# Filamint_Schematic_V4_5.net
KiCad netlist of a schematic drawn in EAGLE
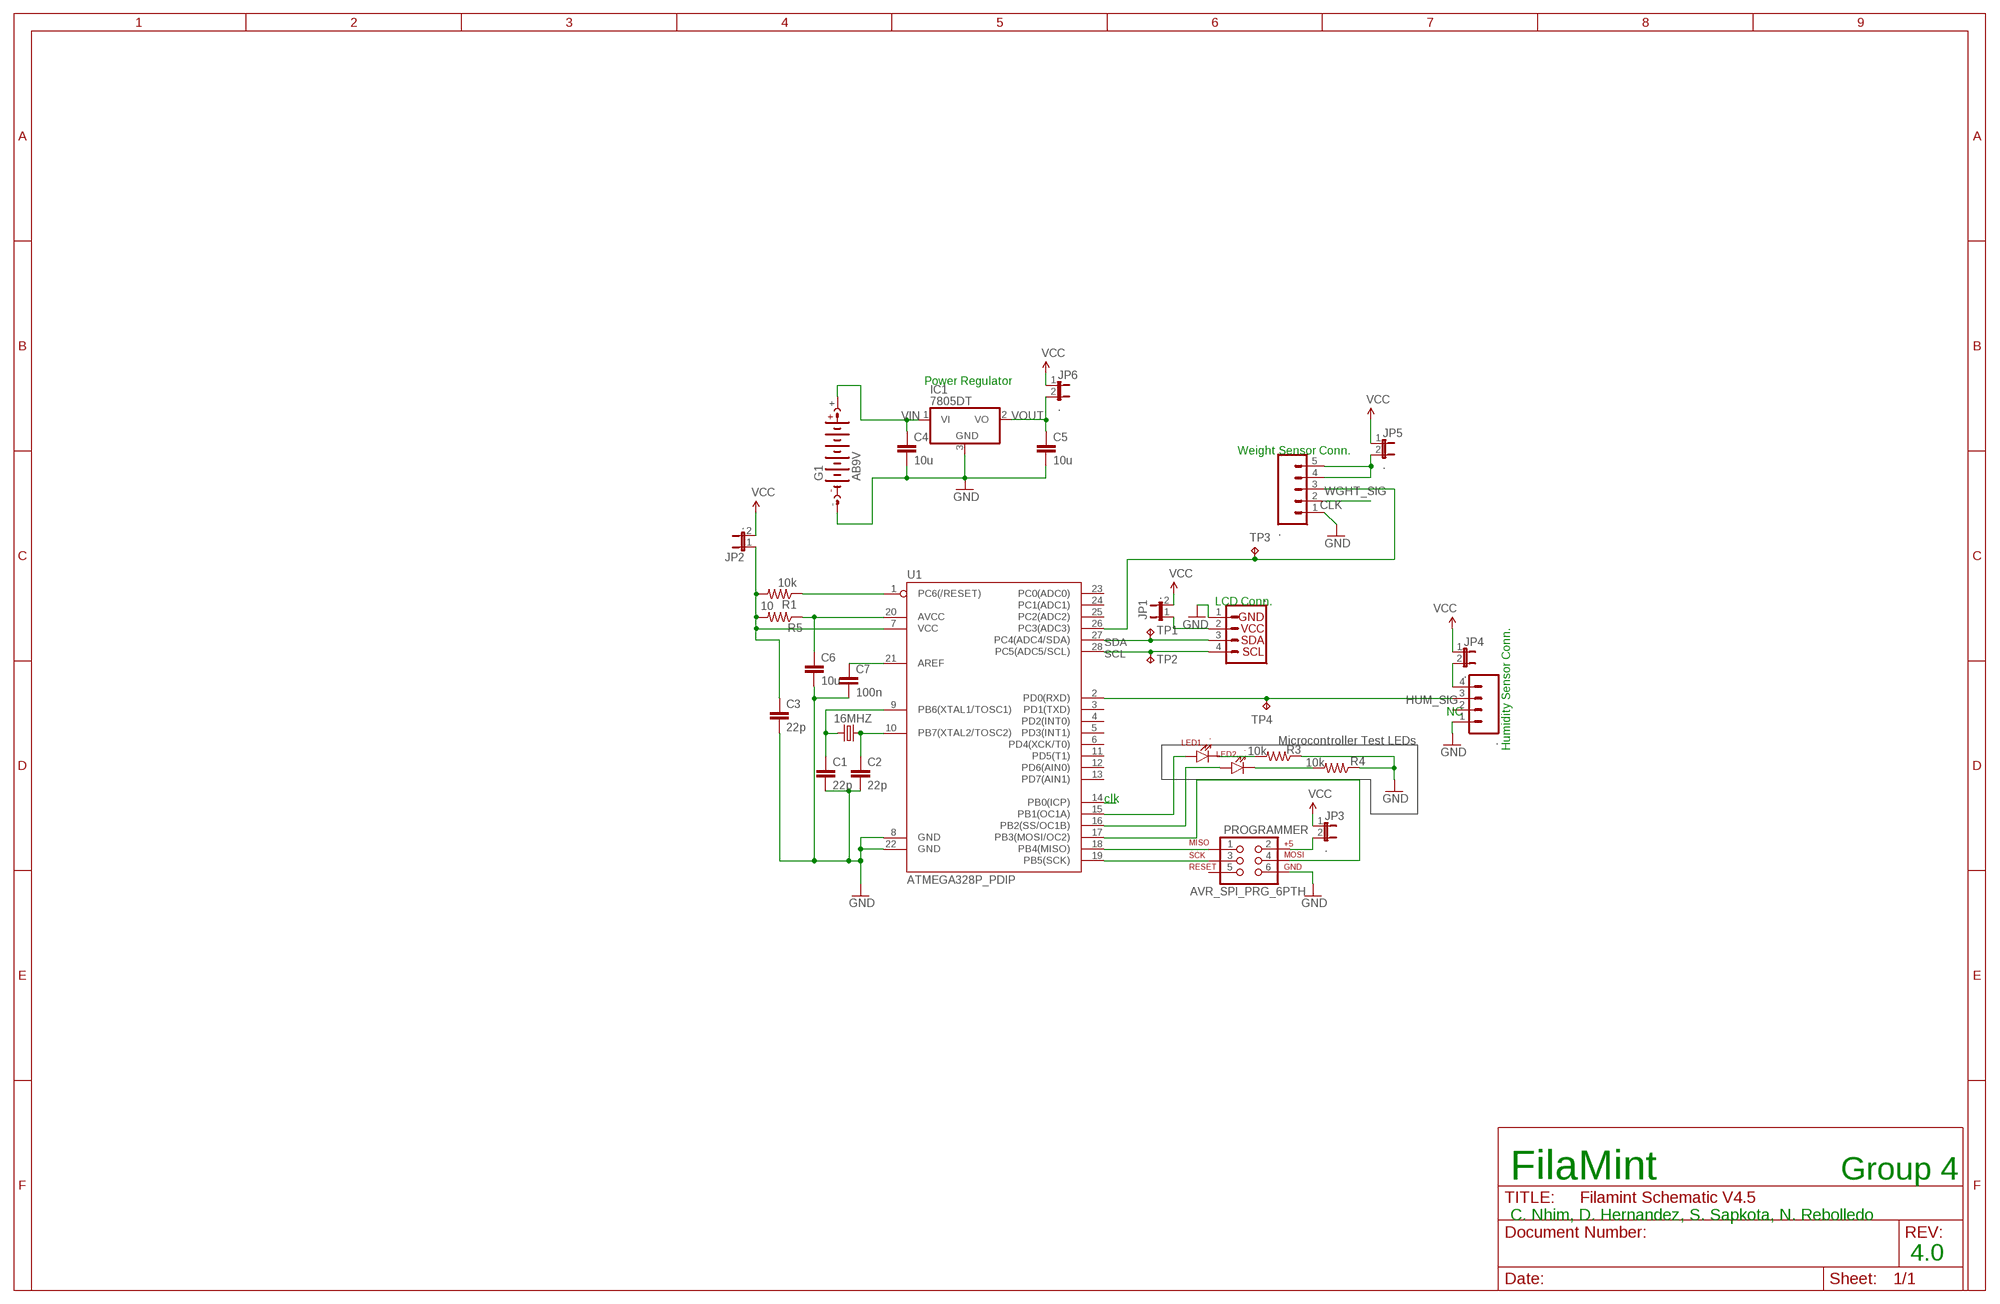
[diagram p0: schematic, sheet 1]

(export (version "E")
  (design (tool "Eeschema 10.0.6"))
  (components
    (comp (ref "16MHZ")
      (value "CSM-7X-DU")
      (footprint "eagle-import:CSM-7X-DU")
      (libsource (lib "eagle-import") (part "CSM-7X-DU"))
    )
    (comp (ref "C1")
      (value "22p")
      (footprint "eagle-import:C025-024X044")
      (libsource (lib "eagle-import") (part "C-EU025-024X044"))
    )
    (comp (ref "C2")
      (value "22p")
      (footprint "eagle-import:C025-024X044")
      (libsource (lib "eagle-import") (part "C-EU025-024X044"))
    )
    (comp (ref "C3")
      (value "22p")
      (footprint "eagle-import:C025-024X044")
      (libsource (lib "eagle-import") (part "C-EU025-024X044"))
    )
    (comp (ref "C4")
      (value "10u")
      (footprint "eagle-import:C025-024X044")
      (libsource (lib "eagle-import") (part "C-EU025-024X044"))
    )
    (comp (ref "C5")
      (value "10u")
      (footprint "eagle-import:C025-024X044")
      (libsource (lib "eagle-import") (part "C-EU025-024X044"))
    )
    (comp (ref "C6")
      (value "10u")
      (footprint "eagle-import:C025-024X044")
      (libsource (lib "eagle-import") (part "C-EU025-024X044"))
    )
    (comp (ref "C7")
      (value "100n")
      (footprint "eagle-import:C025-024X044")
      (libsource (lib "eagle-import") (part "C-EU025-024X044"))
    )
    (comp (ref "DHT22")
      (value ".")
      (footprint "eagle-import:1X04-1MM-RA")
      (libsource (lib "eagle-import") (part "M04SMD2"))
    )
    (comp (ref "G1")
      (value "AB9V")
      (footprint "eagle-import:AB9V")
      (libsource (lib "eagle-import") (part "AB9V"))
    )
    (comp (ref "HX711")
      (value ".")
      (footprint "eagle-import:1X05-1MM")
      (libsource (lib "eagle-import") (part "M05SMD"))
    )
    (comp (ref "IC1")
      (value "7805DT")
      (footprint "eagle-import:TO252")
      (libsource (lib "eagle-import") (part "78DT05"))
    )
    (comp (ref "JP1")
      (value ".")
      (footprint "eagle-import:JP1")
      (libsource (lib "eagle-import") (part "JP1E"))
    )
    (comp (ref "JP2")
      (value ".")
      (footprint "eagle-import:JP1")
      (libsource (lib "eagle-import") (part "JP1E"))
    )
    (comp (ref "JP3")
      (value ".")
      (footprint "eagle-import:JP1")
      (libsource (lib "eagle-import") (part "JP1E"))
    )
    (comp (ref "JP4")
      (value ".")
      (footprint "eagle-import:JP1")
      (libsource (lib "eagle-import") (part "JP1E"))
    )
    (comp (ref "JP5")
      (value ".")
      (footprint "eagle-import:JP1")
      (libsource (lib "eagle-import") (part "JP1E"))
    )
    (comp (ref "JP6")
      (value ".")
      (footprint "eagle-import:JP1")
      (libsource (lib "eagle-import") (part "JP1E"))
    )
    (comp (ref "LCD")
      (value ".")
      (footprint "eagle-import:1X04")
      (libsource (lib "eagle-import") (part "I2C_STANDARD"))
    )
    (comp (ref "LED1")
      (value ".")
      (footprint "eagle-import:LTE-302")
      (libsource (lib "eagle-import") (part "LTE-302"))
    )
    (comp (ref "LED2")
      (value ".")
      (footprint "eagle-import:LTE-302")
      (libsource (lib "eagle-import") (part "LTE-302"))
    )
    (comp (ref "PROGRAMMER")
      (value "AVR_SPI_PRG_6PTH")
      (footprint "eagle-import:2X3")
      (libsource (lib "eagle-import") (part "AVR_SPI_PRG_6PTH"))
    )
    (comp (ref "R1")
      (value "10k")
      (footprint "eagle-import:0204_5")
      (libsource (lib "eagle-import") (part "R-US_0204/5"))
    )
    (comp (ref "R3")
      (value "10k")
      (footprint "eagle-import:0204_5")
      (libsource (lib "eagle-import") (part "R-US_0204/5"))
    )
    (comp (ref "R4")
      (value "10k")
      (footprint "eagle-import:0204_5")
      (libsource (lib "eagle-import") (part "R-US_0204/5"))
    )
    (comp (ref "R5")
      (value "10")
      (footprint "eagle-import:0204_5")
      (libsource (lib "eagle-import") (part "R-US_0204/5"))
    )
    (comp (ref "TP1")
      (value "TPB1,27")
      (footprint "eagle-import:B1,27")
      (libsource (lib "eagle-import") (part "TPB1,27"))
    )
    (comp (ref "TP2")
      (value "TPB1,27")
      (footprint "eagle-import:B1,27")
      (libsource (lib "eagle-import") (part "TPB1,27"))
    )
    (comp (ref "TP3")
      (value "TPB1,27")
      (footprint "eagle-import:B1,27")
      (libsource (lib "eagle-import") (part "TPB1,27"))
    )
    (comp (ref "TP4")
      (value "TPB1,27")
      (footprint "eagle-import:B1,27")
      (libsource (lib "eagle-import") (part "TPB1,27"))
    )
    (comp (ref "U1")
      (value "ATMEGA328P_PDIP")
      (footprint "eagle-import:DIL28-3")
      (libsource (lib "eagle-import") (part "ATMEGA328P_PDIP"))
    )
  )
  (nets
    (net (code "1") (name "/CLK") (class "Default")
      (node (ref "HX711") (pin "2") (pinfunction "2_2") (pintype "passive"))
      (node (ref "U1") (pin "14") (pinfunction "PB0(ICP)_14") (pintype "bidirectional"))
    )
    (net (code "2") (name "/HUM_SIG") (class "Default")
      (node (ref "DHT22") (pin "3") (pinfunction "3_3") (pintype "passive"))
      (node (ref "TP4") (pin "TP") (pinfunction "TP_TP") (pintype "input"))
      (node (ref "U1") (pin "2") (pinfunction "PD0(RXD)_2") (pintype "bidirectional"))
    )
    (net (code "3") (name "/SCL") (class "Default")
      (node (ref "LCD") (pin "4") (pinfunction "4_4") (pintype "passive"))
      (node (ref "TP2") (pin "TP") (pinfunction "TP_TP") (pintype "input"))
      (node (ref "U1") (pin "28") (pinfunction "PC5(ADC5/SCL)_28") (pintype "bidirectional"))
    )
    (net (code "4") (name "/SDA") (class "Default")
      (node (ref "LCD") (pin "3") (pinfunction "3_3") (pintype "passive"))
      (node (ref "TP1") (pin "TP") (pinfunction "TP_TP") (pintype "input"))
      (node (ref "U1") (pin "27") (pinfunction "PC4(ADC4/SDA)_27") (pintype "bidirectional"))
    )
    (net (code "5") (name "/VIN") (class "Default")
      (node (ref "C4") (pin "1") (pinfunction "1_1") (pintype "passive"))
      (node (ref "G1") (pin "+") (pinfunction "+_+") (pintype "passive"))
      (node (ref "IC1") (pin "1") (pinfunction "VI_1") (pintype "input"))
    )
    (net (code "6") (name "/WGHT_SIG") (class "Default")
      (node (ref "HX711") (pin "3") (pinfunction "3_3") (pintype "passive"))
      (node (ref "TP3") (pin "TP") (pinfunction "TP_TP") (pintype "input"))
      (node (ref "U1") (pin "26") (pinfunction "PC3(ADC3)_26") (pintype "bidirectional"))
    )
    (net (code "7") (name "GND") (class "Default")
      (node (ref "C1") (pin "2") (pinfunction "2_2") (pintype "passive"))
      (node (ref "C2") (pin "2") (pinfunction "2_2") (pintype "passive"))
      (node (ref "C3") (pin "2") (pinfunction "2_2") (pintype "passive"))
      (node (ref "C4") (pin "2") (pinfunction "2_2") (pintype "passive"))
      (node (ref "C5") (pin "2") (pinfunction "2_2") (pintype "passive"))
      (node (ref "C6") (pin "2") (pinfunction "2_2") (pintype "passive"))
      (node (ref "C7") (pin "2") (pinfunction "2_2") (pintype "passive"))
      (node (ref "DHT22") (pin "1") (pinfunction "1_1") (pintype "passive"))
      (node (ref "G1") (pin "-") (pinfunction "-_-") (pintype "passive"))
      (node (ref "HX711") (pin "1") (pinfunction "1_1") (pintype "passive"))
      (node (ref "IC1") (pin "3") (pinfunction "GND_3") (pintype "passive"))
      (node (ref "LCD") (pin "1") (pinfunction "1_1") (pintype "passive"))
      (node (ref "PROGRAMMER") (pin "6") (pinfunction "6_6") (pintype "passive"))
      (node (ref "R3") (pin "1") (pinfunction "1_1") (pintype "passive"))
      (node (ref "R4") (pin "1") (pinfunction "1_1") (pintype "passive"))
      (node (ref "U1") (pin "22") (pinfunction "GND_22") (pintype "bidirectional"))
      (node (ref "U1") (pin "8") (pinfunction "GND_8") (pintype "bidirectional"))
    )
    (net (code "8") (name "Net-(DHT22-Pad4)") (class "Default")
      (node (ref "DHT22") (pin "4") (pinfunction "4_4") (pintype "passive"))
      (node (ref "JP4") (pin "2") (pinfunction "2_2") (pintype "passive"))
    )
    (net (code "9") (name "Net-(HX711-Pad4)") (class "Default")
      (node (ref "HX711") (pin "4") (pinfunction "4_4") (pintype "passive"))
      (node (ref "HX711") (pin "5") (pinfunction "5_5") (pintype "passive"))
      (node (ref "JP5") (pin "2") (pinfunction "2_2") (pintype "passive"))
    )
    (net (code "10") (name "Net-(IC1-VO)") (class "Default")
      (node (ref "C5") (pin "1") (pinfunction "1_1") (pintype "passive"))
      (node (ref "IC1") (pin "2") (pinfunction "VO_2") (pintype "passive"))
      (node (ref "JP6") (pin "2") (pinfunction "2_2") (pintype "passive"))
    )
    (net (code "11") (name "Net-(JP1-Pad1)") (class "Default")
      (node (ref "JP1") (pin "1") (pinfunction "1_1") (pintype "passive"))
      (node (ref "LCD") (pin "2") (pinfunction "2_2") (pintype "passive"))
    )
    (net (code "12") (name "Net-(JP3-Pad2)") (class "Default")
      (node (ref "JP3") (pin "2") (pinfunction "2_2") (pintype "passive"))
      (node (ref "PROGRAMMER") (pin "2") (pinfunction "2_2") (pintype "passive"))
    )
    (net (code "13") (name "Net-(LED1-PadC)") (class "Default")
      (node (ref "LED1") (pin "C") (pinfunction "C_C") (pintype "bidirectional"))
      (node (ref "R3") (pin "2") (pinfunction "2_2") (pintype "passive"))
    )
    (net (code "14") (name "Net-(LED2-PadC)") (class "Default")
      (node (ref "LED2") (pin "C") (pinfunction "C_C") (pintype "bidirectional"))
      (node (ref "R4") (pin "2") (pinfunction "2_2") (pintype "passive"))
    )
    (net (code "15") (name "Net-(U1-AREF)") (class "Default")
      (node (ref "C7") (pin "1") (pinfunction "1_1") (pintype "passive"))
      (node (ref "U1") (pin "21") (pinfunction "AREF_21") (pintype "bidirectional"))
    )
    (net (code "16") (name "Net-(U1-AVCC)") (class "Default")
      (node (ref "C6") (pin "1") (pinfunction "1_1") (pintype "passive"))
      (node (ref "R5") (pin "1") (pinfunction "1_1") (pintype "passive"))
      (node (ref "U1") (pin "20") (pinfunction "AVCC_20") (pintype "bidirectional"))
    )
    (net (code "17") (name "Net-(U1-PB1(OC1A))") (class "Default")
      (node (ref "LED1") (pin "A") (pinfunction "A_A") (pintype "bidirectional"))
      (node (ref "U1") (pin "15") (pinfunction "PB1(OC1A)_15") (pintype "bidirectional"))
    )
    (net (code "18") (name "Net-(U1-PB2(SS{slash}OC1B))") (class "Default")
      (node (ref "LED2") (pin "A") (pinfunction "A_A") (pintype "bidirectional"))
      (node (ref "U1") (pin "16") (pinfunction "PB2(SS/OC1B)_16") (pintype "bidirectional"))
    )
    (net (code "19") (name "Net-(U1-PB3(MOSI{slash}OC2))") (class "Default")
      (node (ref "PROGRAMMER") (pin "4") (pinfunction "4_4") (pintype "passive"))
      (node (ref "U1") (pin "17") (pinfunction "PB3(MOSI/OC2)_17") (pintype "bidirectional"))
    )
    (net (code "20") (name "Net-(U1-PB4(MISO))") (class "Default")
      (node (ref "PROGRAMMER") (pin "1") (pinfunction "1_1") (pintype "passive"))
      (node (ref "U1") (pin "18") (pinfunction "PB4(MISO)_18") (pintype "bidirectional"))
    )
    (net (code "21") (name "Net-(U1-PB5(SCK))") (class "Default")
      (node (ref "PROGRAMMER") (pin "3") (pinfunction "3_3") (pintype "passive"))
      (node (ref "U1") (pin "19") (pinfunction "PB5(SCK)_19") (pintype "bidirectional"))
    )
    (net (code "22") (name "Net-(U1-PB6(XTAL1{slash}TOSC1))") (class "Default")
      (node (ref "16MHZ") (pin "2") (pinfunction "2_2") (pintype "passive"))
      (node (ref "C1") (pin "1") (pinfunction "1_1") (pintype "passive"))
      (node (ref "U1") (pin "9") (pinfunction "PB6(XTAL1/TOSC1)_9") (pintype "bidirectional"))
    )
    (net (code "23") (name "Net-(U1-PB7(XTAL2{slash}TOSC2))") (class "Default")
      (node (ref "16MHZ") (pin "1") (pinfunction "1_1") (pintype "passive"))
      (node (ref "C2") (pin "1") (pinfunction "1_1") (pintype "passive"))
      (node (ref "U1") (pin "10") (pinfunction "PB7(XTAL2/TOSC2)_10") (pintype "bidirectional"))
    )
    (net (code "24") (name "Net-(U1-PC6({slash}RESET))") (class "Default")
      (node (ref "R1") (pin "1") (pinfunction "1_1") (pintype "passive"))
      (node (ref "U1") (pin "1") (pinfunction "PC6(/RESET)_1") (pintype "bidirectional"))
    )
    (net (code "25") (name "Net-(U1-VCC)") (class "Default")
      (node (ref "C3") (pin "1") (pinfunction "1_1") (pintype "passive"))
      (node (ref "JP2") (pin "1") (pinfunction "1_1") (pintype "passive"))
      (node (ref "R1") (pin "2") (pinfunction "2_2") (pintype "passive"))
      (node (ref "R5") (pin "2") (pinfunction "2_2") (pintype "passive"))
      (node (ref "U1") (pin "7") (pinfunction "VCC_7") (pintype "bidirectional"))
    )
    (net (code "26") (name "VCC") (class "Default")
      (node (ref "JP1") (pin "2") (pinfunction "2_2") (pintype "passive"))
      (node (ref "JP2") (pin "2") (pinfunction "2_2") (pintype "passive"))
      (node (ref "JP3") (pin "1") (pinfunction "1_1") (pintype "passive"))
      (node (ref "JP4") (pin "1") (pinfunction "1_1") (pintype "passive"))
      (node (ref "JP5") (pin "1") (pinfunction "1_1") (pintype "passive"))
      (node (ref "JP6") (pin "1") (pinfunction "1_1") (pintype "passive"))
    )
    (net (code "27") (name "unconnected-(DHT22-Pad2)") (class "Default")
      (node (ref "DHT22") (pin "2") (pinfunction "2_2") (pintype "passive"))
    )
    (net (code "28") (name "unconnected-(PROGRAMMER-Pad5)") (class "Default")
      (node (ref "PROGRAMMER") (pin "5") (pinfunction "5_5") (pintype "passive"))
    )
    (net (code "29") (name "unconnected-(U1-PC0(ADC0)-Pad23)") (class "Default")
      (node (ref "U1") (pin "23") (pinfunction "PC0(ADC0)_23") (pintype "bidirectional"))
    )
    (net (code "30") (name "unconnected-(U1-PC1(ADC1)-Pad24)") (class "Default")
      (node (ref "U1") (pin "24") (pinfunction "PC1(ADC1)_24") (pintype "bidirectional"))
    )
    (net (code "31") (name "unconnected-(U1-PC2(ADC2)-Pad25)") (class "Default")
      (node (ref "U1") (pin "25") (pinfunction "PC2(ADC2)_25") (pintype "bidirectional"))
    )
    (net (code "32") (name "unconnected-(U1-PD1(TXD)-Pad3)") (class "Default")
      (node (ref "U1") (pin "3") (pinfunction "PD1(TXD)_3") (pintype "bidirectional"))
    )
    (net (code "33") (name "unconnected-(U1-PD2(INT0)-Pad4)") (class "Default")
      (node (ref "U1") (pin "4") (pinfunction "PD2(INT0)_4") (pintype "bidirectional"))
    )
    (net (code "34") (name "unconnected-(U1-PD3(INT1)-Pad5)") (class "Default")
      (node (ref "U1") (pin "5") (pinfunction "PD3(INT1)_5") (pintype "bidirectional"))
    )
    (net (code "35") (name "unconnected-(U1-PD4(XCK{slash}T0)-Pad6)") (class "Default")
      (node (ref "U1") (pin "6") (pinfunction "PD4(XCK/T0)_6") (pintype "bidirectional"))
    )
    (net (code "36") (name "unconnected-(U1-PD5(T1)-Pad11)") (class "Default")
      (node (ref "U1") (pin "11") (pinfunction "PD5(T1)_11") (pintype "bidirectional"))
    )
    (net (code "37") (name "unconnected-(U1-PD6(AIN0)-Pad12)") (class "Default")
      (node (ref "U1") (pin "12") (pinfunction "PD6(AIN0)_12") (pintype "bidirectional"))
    )
    (net (code "38") (name "unconnected-(U1-PD7(AIN1)-Pad13)") (class "Default")
      (node (ref "U1") (pin "13") (pinfunction "PD7(AIN1)_13") (pintype "bidirectional"))
    )
  )
)
